# meld_fb.net
KiCad netlist of a schematic drawn in EAGLE
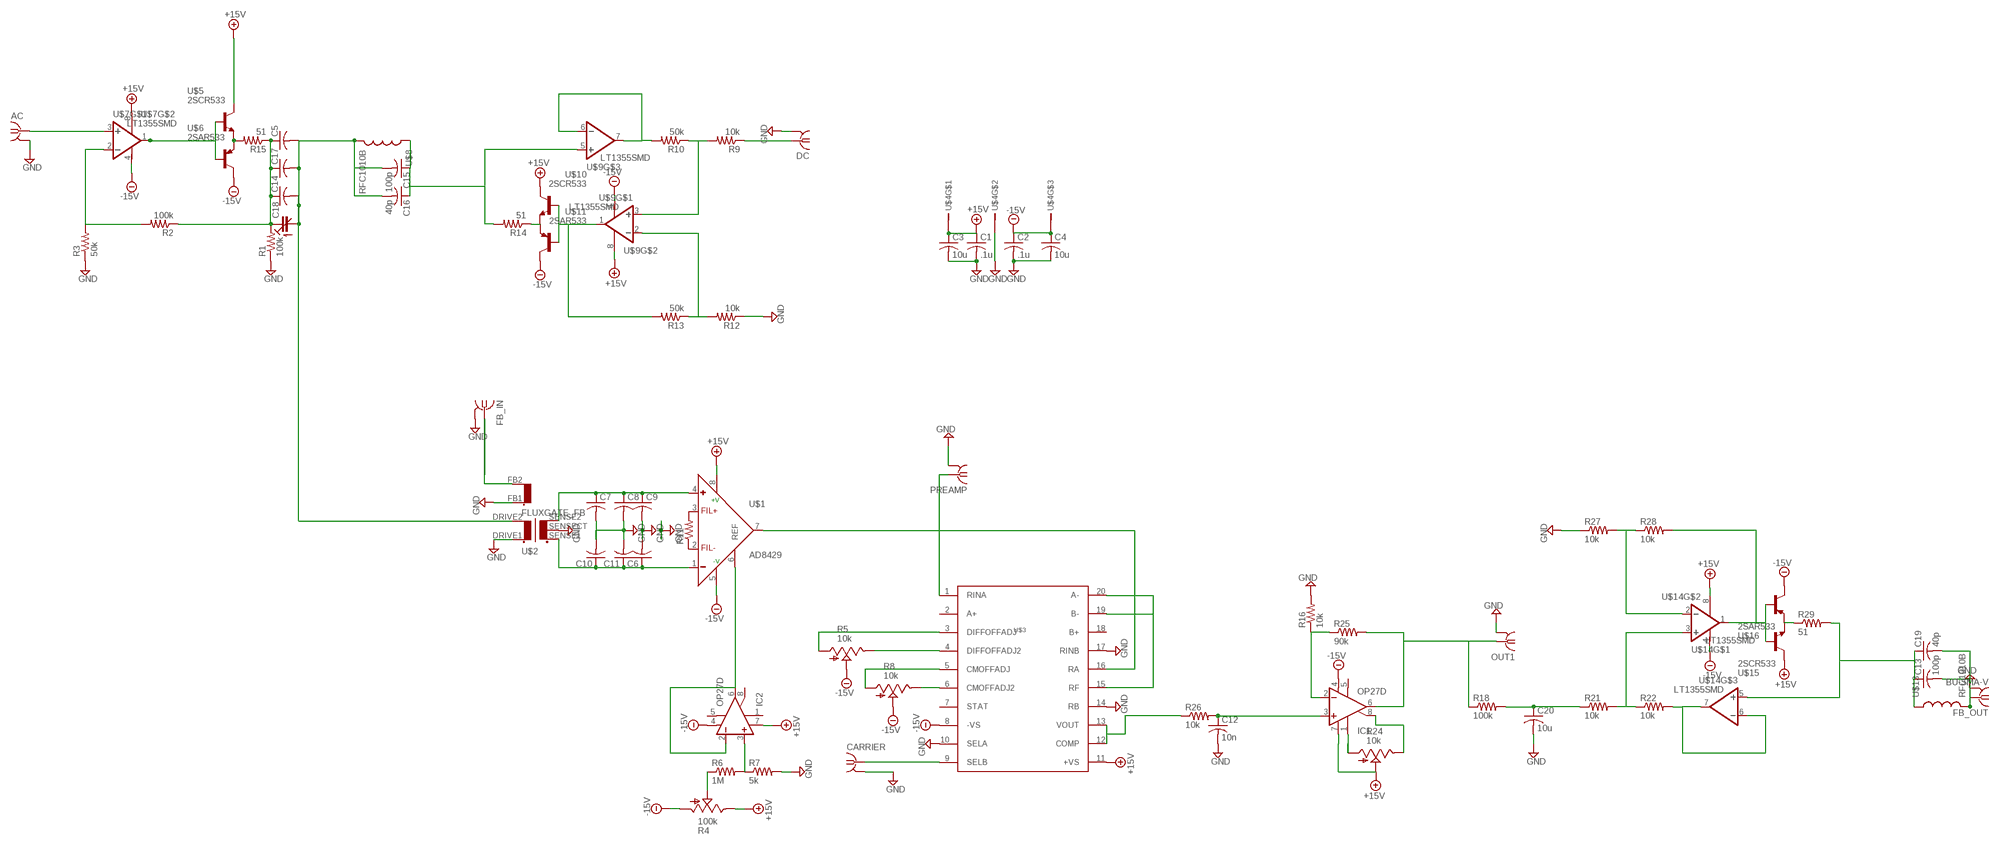
[diagram p0: schematic, sheet 1]

(export (version "E")
  (design (tool "Eeschema 10.0.6"))
  (components
    (comp (ref "AC")
      (value "SMA-142-0701-851/861")
      (footprint "eagle-import:J502-ND-142-0701-851_861")
      (fields (field (name "MF") "JOHNSON COMPONENTS") (field (name "MPN") "142-0701-851"))
      (libsource (lib "eagle-import") (part "SMA-142-0701-851/861"))
    )
    (comp (ref "C1")
      (value ".1u")
      (footprint "eagle-import:C1206")
      (libsource (lib "eagle-import") (part "C-USC1206"))
    )
    (comp (ref "C2")
      (value ".1u")
      (footprint "eagle-import:C1206")
      (libsource (lib "eagle-import") (part "C-USC1206"))
    )
    (comp (ref "C3")
      (value "10u")
      (footprint "eagle-import:C1206")
      (libsource (lib "eagle-import") (part "C-USC1206"))
    )
    (comp (ref "C4")
      (value "10u")
      (footprint "eagle-import:C1206")
      (libsource (lib "eagle-import") (part "C-USC1206"))
    )
    (comp (ref "C5")
      (value "C-USC0805")
      (footprint "eagle-import:C0805")
      (libsource (lib "eagle-import") (part "C-USC0805"))
    )
    (comp (ref "C6")
      (value "C-USC0805")
      (footprint "eagle-import:C0805")
      (libsource (lib "eagle-import") (part "C-USC0805"))
    )
    (comp (ref "C7")
      (value "C-USC0805")
      (footprint "eagle-import:C0805")
      (libsource (lib "eagle-import") (part "C-USC0805"))
    )
    (comp (ref "C8")
      (value "C-USC0805")
      (footprint "eagle-import:C0805")
      (libsource (lib "eagle-import") (part "C-USC0805"))
    )
    (comp (ref "C9")
      (value "C-USC0805")
      (footprint "eagle-import:C0805")
      (libsource (lib "eagle-import") (part "C-USC0805"))
    )
    (comp (ref "C10")
      (value "C-USC0805")
      (footprint "eagle-import:C0805")
      (libsource (lib "eagle-import") (part "C-USC0805"))
    )
    (comp (ref "C11")
      (value "C-USC0805")
      (footprint "eagle-import:C0805")
      (libsource (lib "eagle-import") (part "C-USC0805"))
    )
    (comp (ref "C12")
      (value "10n")
      (footprint "eagle-import:C0805")
      (libsource (lib "eagle-import") (part "C-USC0805"))
    )
    (comp (ref "C13")
      (value "100p")
      (footprint "eagle-import:C0805")
      (libsource (lib "eagle-import") (part "C-USC0805"))
    )
    (comp (ref "C14")
      (value "C-USC0805")
      (footprint "eagle-import:C0805")
      (libsource (lib "eagle-import") (part "C-USC0805"))
    )
    (comp (ref "C15")
      (value "100p")
      (footprint "eagle-import:C0805")
      (libsource (lib "eagle-import") (part "C-USC0805"))
    )
    (comp (ref "C16")
      (value "40p")
      (footprint "eagle-import:C0805")
      (libsource (lib "eagle-import") (part "C-USC0805"))
    )
    (comp (ref "C17")
      (value "C-USC0805")
      (footprint "eagle-import:C0805")
      (libsource (lib "eagle-import") (part "C-USC0805"))
    )
    (comp (ref "C18")
      (value "C-TRIMM")
      (footprint "eagle-import:SGC3S")
      (libsource (lib "eagle-import") (part "C-TRIMM"))
    )
    (comp (ref "C19")
      (value "40p")
      (footprint "eagle-import:C0805")
      (libsource (lib "eagle-import") (part "C-USC0805"))
    )
    (comp (ref "C20")
      (value "10u")
      (footprint "eagle-import:C1206")
      (libsource (lib "eagle-import") (part "C-USC1206"))
    )
    (comp (ref "CARRIER")
      (value "SMA-142-0701-851/861")
      (footprint "eagle-import:J502-ND-142-0701-851_861")
      (fields (field (name "MF") "JOHNSON COMPONENTS") (field (name "MPN") "142-0701-851"))
      (libsource (lib "eagle-import") (part "SMA-142-0701-851/861"))
    )
    (comp (ref "DC")
      (value "SMA-142-0701-851/861")
      (footprint "eagle-import:J502-ND-142-0701-851_861")
      (fields (field (name "MF") "JOHNSON COMPONENTS") (field (name "MPN") "142-0701-851"))
      (libsource (lib "eagle-import") (part "SMA-142-0701-851/861"))
    )
    (comp (ref "FB_IN")
      (value "SMA-142-0701-851/861")
      (footprint "eagle-import:J502-ND-142-0701-851_861")
      (fields (field (name "MF") "JOHNSON COMPONENTS") (field (name "MPN") "142-0701-851"))
      (libsource (lib "eagle-import") (part "SMA-142-0701-851/861"))
    )
    (comp (ref "FB_OUT")
      (value "BU-SMA-V")
      (footprint "eagle-import:BU-SMA-V")
      (libsource (lib "eagle-import") (part "BU-SMA-V"))
    )
    (comp (ref "IC1")
      (value "OP27D")
      (footprint "eagle-import:SO08")
      (libsource (lib "eagle-import") (part "OP27D"))
    )
    (comp (ref "IC2")
      (value "OP27D")
      (footprint "eagle-import:SO08")
      (libsource (lib "eagle-import") (part "OP27D"))
    )
    (comp (ref "OUT1")
      (value "SMA-142-0701-851/861")
      (footprint "eagle-import:J502-ND-142-0701-851_861")
      (fields (field (name "MF") "JOHNSON COMPONENTS") (field (name "MPN") "142-0701-851"))
      (libsource (lib "eagle-import") (part "SMA-142-0701-851/861"))
    )
    (comp (ref "PREAMP")
      (value "SMA-142-0701-851/861")
      (footprint "eagle-import:J502-ND-142-0701-851_861")
      (fields (field (name "MF") "JOHNSON COMPONENTS") (field (name "MPN") "142-0701-851"))
      (libsource (lib "eagle-import") (part "SMA-142-0701-851/861"))
    )
    (comp (ref "R1")
      (value "100k")
      (footprint "eagle-import:R0805")
      (libsource (lib "eagle-import") (part "R-US_R0805"))
    )
    (comp (ref "R2")
      (value "100k")
      (footprint "eagle-import:R0805")
      (libsource (lib "eagle-import") (part "R-US_R0805"))
    )
    (comp (ref "R3")
      (value "50k")
      (footprint "eagle-import:R0805")
      (libsource (lib "eagle-import") (part "R-US_R0805"))
    )
    (comp (ref "R4")
      (value "100k")
      (footprint "eagle-import:B64Y")
      (libsource (lib "eagle-import") (part "TRIM_US-B64Y"))
    )
    (comp (ref "R5")
      (value "10k")
      (footprint "eagle-import:B64Y")
      (libsource (lib "eagle-import") (part "TRIM_US-B64Y"))
    )
    (comp (ref "R6")
      (value "1M")
      (footprint "eagle-import:R0805")
      (libsource (lib "eagle-import") (part "R-US_R0805"))
    )
    (comp (ref "R7")
      (value "5k")
      (footprint "eagle-import:R0805")
      (libsource (lib "eagle-import") (part "R-US_R0805"))
    )
    (comp (ref "R8")
      (value "10k")
      (footprint "eagle-import:B64Y")
      (libsource (lib "eagle-import") (part "TRIM_US-B64Y"))
    )
    (comp (ref "R9")
      (value "10k")
      (footprint "eagle-import:R0805")
      (libsource (lib "eagle-import") (part "R-US_R0805"))
    )
    (comp (ref "R10")
      (value "50k")
      (footprint "eagle-import:R0805")
      (libsource (lib "eagle-import") (part "R-US_R0805"))
    )
    (comp (ref "R11")
      (value "R-US_R0805")
      (footprint "eagle-import:R0805")
      (libsource (lib "eagle-import") (part "R-US_R0805"))
    )
    (comp (ref "R12")
      (value "10k")
      (footprint "eagle-import:R0805")
      (libsource (lib "eagle-import") (part "R-US_R0805"))
    )
    (comp (ref "R13")
      (value "50k")
      (footprint "eagle-import:R0805")
      (libsource (lib "eagle-import") (part "R-US_R0805"))
    )
    (comp (ref "R14")
      (value "51")
      (footprint "eagle-import:R2512")
      (libsource (lib "eagle-import") (part "R-US_R2512"))
    )
    (comp (ref "R15")
      (value "51")
      (footprint "eagle-import:R2512")
      (libsource (lib "eagle-import") (part "R-US_R2512"))
    )
    (comp (ref "R16")
      (value "10k")
      (footprint "eagle-import:R0805")
      (libsource (lib "eagle-import") (part "resistor_R-US_R0805"))
    )
    (comp (ref "R18")
      (value "100k")
      (footprint "eagle-import:R0805")
      (libsource (lib "eagle-import") (part "resistor_R-US_R0805"))
    )
    (comp (ref "R21")
      (value "10k")
      (footprint "eagle-import:R0805")
      (libsource (lib "eagle-import") (part "R-US_R0805"))
    )
    (comp (ref "R22")
      (value "10k")
      (footprint "eagle-import:R0805")
      (libsource (lib "eagle-import") (part "R-US_R0805"))
    )
    (comp (ref "R24")
      (value "10k")
      (footprint "eagle-import:B64Y")
      (libsource (lib "eagle-import") (part "TRIM_US-B64Y"))
    )
    (comp (ref "R25")
      (value "90k")
      (footprint "eagle-import:R0805")
      (libsource (lib "eagle-import") (part "resistor_R-US_R0805"))
    )
    (comp (ref "R26")
      (value "10k")
      (footprint "eagle-import:R0805")
      (libsource (lib "eagle-import") (part "resistor_R-US_R0805"))
    )
    (comp (ref "R27")
      (value "10k")
      (footprint "eagle-import:R0805")
      (libsource (lib "eagle-import") (part "R-US_R0805"))
    )
    (comp (ref "R28")
      (value "10k")
      (footprint "eagle-import:R0805")
      (libsource (lib "eagle-import") (part "R-US_R0805"))
    )
    (comp (ref "R29")
      (value "51")
      (footprint "eagle-import:R2512")
      (libsource (lib "eagle-import") (part "R-US_R2512"))
    )
    (comp (ref "U$1")
      (value "AD8429")
      (footprint "eagle-import:SO8")
      (libsource (lib "eagle-import") (part "AD8428"))
    )
    (comp (ref "U$2")
      (value "FLUXGATE_FB")
      (footprint "eagle-import:PARA_FB")
      (libsource (lib "eagle-import") (part "FLUXGATE_FB"))
    )
    (comp (ref "U$3")
      (value "AD630")
      (footprint "eagle-import:SOIC20R")
      (libsource (lib "eagle-import") (part "AD630"))
    )
    (comp (ref "U$4")
      (value "B3B-AM")
      (footprint "eagle-import:B3B-AM")
      (libsource (lib "eagle-import") (part "B3B-AM"))
    )
    (comp (ref "U$5")
      (value "2SCR533")
      (footprint "eagle-import:SOT89-BCE")
      (libsource (lib "eagle-import") (part "2SCR533"))
    )
    (comp (ref "U$6")
      (value "2SAR533")
      (footprint "eagle-import:SOT89-BCE")
      (libsource (lib "eagle-import") (part "2SAR533"))
    )
    (comp (ref "U$7")
      (value "LT1355SMD")
      (footprint "eagle-import:SOIC8")
      (libsource (lib "eagle-import") (part "LT1355SMD"))
    )
    (comp (ref "U$8")
      (value "RFC1010B")
      (footprint "eagle-import:186KE")
      (libsource (lib "eagle-import") (part "RFC1010B"))
    )
    (comp (ref "U$9")
      (value "LT1355SMD")
      (footprint "eagle-import:SOIC8")
      (libsource (lib "eagle-import") (part "LT1355SMD"))
    )
    (comp (ref "U$10")
      (value "2SCR533")
      (footprint "eagle-import:SOT89-BCE")
      (libsource (lib "eagle-import") (part "2SCR533"))
    )
    (comp (ref "U$11")
      (value "2SAR533")
      (footprint "eagle-import:SOT89-BCE")
      (libsource (lib "eagle-import") (part "2SAR533"))
    )
    (comp (ref "U$13")
      (value "RFC1010B")
      (footprint "eagle-import:186KE")
      (libsource (lib "eagle-import") (part "RFC1010B"))
    )
    (comp (ref "U$14")
      (value "LT1355SMD")
      (footprint "eagle-import:SOIC8")
      (libsource (lib "eagle-import") (part "LT1355SMD"))
    )
    (comp (ref "U$15")
      (value "2SCR533")
      (footprint "eagle-import:SOT89-BCE")
      (libsource (lib "eagle-import") (part "2SCR533"))
    )
    (comp (ref "U$16")
      (value "2SAR533")
      (footprint "eagle-import:SOT89-BCE")
      (libsource (lib "eagle-import") (part "2SAR533"))
    )
  )
  (nets
    (net (code "1") (name "+15V") (class "Default")
      (node (ref "C1") (pin "1") (pinfunction "1_1") (pintype "passive"))
      (node (ref "C3") (pin "1") (pinfunction "1_1") (pintype "passive"))
      (node (ref "IC1") (pin "7") (pinfunction "V+_7") (pintype "power_in"))
      (node (ref "IC2") (pin "7") (pinfunction "V+_7") (pintype "power_in"))
      (node (ref "R24") (pin "S") (pinfunction "S_S") (pintype "passive"))
      (node (ref "R4") (pin "E") (pinfunction "E_E") (pintype "passive"))
      (node (ref "U$1") (pin "8") (pinfunction "+V_8") (pintype "power_in"))
      (node (ref "U$10") (pin "C") (pinfunction "C_C") (pintype "passive"))
      (node (ref "U$14") (pin "8") (pinfunction "V+_8") (pintype "power_in"))
      (node (ref "U$15") (pin "C") (pinfunction "C_C") (pintype "passive"))
      (node (ref "U$3") (pin "11") (pinfunction "+VS_11") (pintype "bidirectional"))
      (node (ref "U$4") (pin "1") (pinfunction "1_1") (pintype "passive"))
      (node (ref "U$5") (pin "C") (pinfunction "C_C") (pintype "passive"))
      (node (ref "U$7") (pin "8") (pinfunction "V+_8") (pintype "power_in"))
      (node (ref "U$9") (pin "8") (pinfunction "V+_8") (pintype "power_in"))
    )
    (net (code "2") (name "-15V") (class "Default")
      (node (ref "C2") (pin "1") (pinfunction "1_1") (pintype "passive"))
      (node (ref "C4") (pin "1") (pinfunction "1_1") (pintype "passive"))
      (node (ref "IC1") (pin "4") (pinfunction "V-_4") (pintype "power_in"))
      (node (ref "IC2") (pin "4") (pinfunction "V-_4") (pintype "power_in"))
      (node (ref "R4") (pin "A") (pinfunction "A_A") (pintype "passive"))
      (node (ref "R5") (pin "S") (pinfunction "S_S") (pintype "passive"))
      (node (ref "R8") (pin "S") (pinfunction "S_S") (pintype "passive"))
      (node (ref "U$1") (pin "5") (pinfunction "-V_5") (pintype "power_in"))
      (node (ref "U$11") (pin "C") (pinfunction "C_C") (pintype "passive"))
      (node (ref "U$14") (pin "4") (pinfunction "V-_4") (pintype "power_in"))
      (node (ref "U$16") (pin "C") (pinfunction "C_C") (pintype "passive"))
      (node (ref "U$3") (pin "8") (pinfunction "-VS_8") (pintype "bidirectional"))
      (node (ref "U$4") (pin "3") (pinfunction "1_3") (pintype "passive"))
      (node (ref "U$6") (pin "C") (pinfunction "C_C") (pintype "passive"))
      (node (ref "U$7") (pin "4") (pinfunction "V-_4") (pintype "power_in"))
      (node (ref "U$9") (pin "4") (pinfunction "V-_4") (pintype "power_in"))
    )
    (net (code "3") (name "GND") (class "Default")
      (node (ref "AC") (pin "G@1") (pinfunction "2_G@1") (pintype "passive"))
      (node (ref "AC") (pin "G@2") (pinfunction "2_G@2") (pintype "passive"))
      (node (ref "AC") (pin "G@3") (pinfunction "2_G@3") (pintype "passive"))
      (node (ref "AC") (pin "G@4") (pinfunction "2_G@4") (pintype "passive"))
      (node (ref "C1") (pin "2") (pinfunction "2_2") (pintype "passive"))
      (node (ref "C10") (pin "2") (pinfunction "2_2") (pintype "passive"))
      (node (ref "C11") (pin "2") (pinfunction "2_2") (pintype "passive"))
      (node (ref "C12") (pin "2") (pinfunction "2_2") (pintype "passive"))
      (node (ref "C2") (pin "2") (pinfunction "2_2") (pintype "passive"))
      (node (ref "C20") (pin "2") (pinfunction "2_2") (pintype "passive"))
      (node (ref "C3") (pin "2") (pinfunction "2_2") (pintype "passive"))
      (node (ref "C4") (pin "2") (pinfunction "2_2") (pintype "passive"))
      (node (ref "C6") (pin "2") (pinfunction "2_2") (pintype "passive"))
      (node (ref "C7") (pin "2") (pinfunction "2_2") (pintype "passive"))
      (node (ref "C8") (pin "2") (pinfunction "2_2") (pintype "passive"))
      (node (ref "C9") (pin "2") (pinfunction "2_2") (pintype "passive"))
      (node (ref "CARRIER") (pin "G@1") (pinfunction "2_G@1") (pintype "passive"))
      (node (ref "CARRIER") (pin "G@2") (pinfunction "2_G@2") (pintype "passive"))
      (node (ref "CARRIER") (pin "G@3") (pinfunction "2_G@3") (pintype "passive"))
      (node (ref "CARRIER") (pin "G@4") (pinfunction "2_G@4") (pintype "passive"))
      (node (ref "DC") (pin "G@1") (pinfunction "2_G@1") (pintype "passive"))
      (node (ref "DC") (pin "G@2") (pinfunction "2_G@2") (pintype "passive"))
      (node (ref "DC") (pin "G@3") (pinfunction "2_G@3") (pintype "passive"))
      (node (ref "DC") (pin "G@4") (pinfunction "2_G@4") (pintype "passive"))
      (node (ref "FB_IN") (pin "G@1") (pinfunction "2_G@1") (pintype "passive"))
      (node (ref "FB_IN") (pin "G@2") (pinfunction "2_G@2") (pintype "passive"))
      (node (ref "FB_IN") (pin "G@3") (pinfunction "2_G@3") (pintype "passive"))
      (node (ref "FB_IN") (pin "G@4") (pinfunction "2_G@4") (pintype "passive"))
      (node (ref "FB_OUT") (pin "2") (pinfunction "2_2") (pintype "passive"))
      (node (ref "FB_OUT") (pin "3") (pinfunction "2_3") (pintype "passive"))
      (node (ref "FB_OUT") (pin "4") (pinfunction "2_4") (pintype "passive"))
      (node (ref "FB_OUT") (pin "5") (pinfunction "2_5") (pintype "passive"))
      (node (ref "OUT1") (pin "G@1") (pinfunction "2_G@1") (pintype "passive"))
      (node (ref "OUT1") (pin "G@2") (pinfunction "2_G@2") (pintype "passive"))
      (node (ref "OUT1") (pin "G@3") (pinfunction "2_G@3") (pintype "passive"))
      (node (ref "OUT1") (pin "G@4") (pinfunction "2_G@4") (pintype "passive"))
      (node (ref "PREAMP") (pin "G@1") (pinfunction "2_G@1") (pintype "passive"))
      (node (ref "PREAMP") (pin "G@2") (pinfunction "2_G@2") (pintype "passive"))
      (node (ref "PREAMP") (pin "G@3") (pinfunction "2_G@3") (pintype "passive"))
      (node (ref "PREAMP") (pin "G@4") (pinfunction "2_G@4") (pintype "passive"))
      (node (ref "R1") (pin "1") (pinfunction "1_1") (pintype "passive"))
      (node (ref "R12") (pin "1") (pinfunction "1_1") (pintype "passive"))
      (node (ref "R16") (pin "2") (pinfunction "2_2") (pintype "passive"))
      (node (ref "R27") (pin "1") (pinfunction "1_1") (pintype "passive"))
      (node (ref "R3") (pin "1") (pinfunction "1_1") (pintype "passive"))
      (node (ref "R7") (pin "2") (pinfunction "2_2") (pintype "passive"))
      (node (ref "U$2") (pin "DRIVE1") (pinfunction "1_DRIVE1") (pintype "passive"))
      (node (ref "U$2") (pin "FB1") (pinfunction "6_FB1") (pintype "passive"))
      (node (ref "U$2") (pin "SENSECT") (pinfunction "4_SENSECT") (pintype "passive"))
      (node (ref "U$3") (pin "10") (pinfunction "SELA_10") (pintype "bidirectional"))
      (node (ref "U$3") (pin "14") (pinfunction "RB_14") (pintype "bidirectional"))
      (node (ref "U$3") (pin "17") (pinfunction "RINB_17") (pintype "bidirectional"))
      (node (ref "U$4") (pin "2") (pinfunction "1_2") (pintype "passive"))
    )
    (net (code "4") (name "Net-(C18-A)") (class "Default")
      (node (ref "C14") (pin "2") (pinfunction "2_2") (pintype "passive"))
      (node (ref "C15") (pin "2") (pinfunction "2_2") (pintype "passive"))
      (node (ref "C16") (pin "2") (pinfunction "2_2") (pintype "passive"))
      (node (ref "C17") (pin "2") (pinfunction "2_2") (pintype "passive"))
      (node (ref "C18") (pin "P$1") (pinfunction "A_P$1") (pintype "passive"))
      (node (ref "C5") (pin "2") (pinfunction "2_2") (pintype "passive"))
      (node (ref "U$2") (pin "DRIVE2") (pinfunction "2_DRIVE2") (pintype "passive"))
      (node (ref "U$8") (pin "P$2") (pinfunction "2_P$2") (pintype "passive"))
    )
    (net (code "5") (name "Net-(C18-E)") (class "Default")
      (node (ref "C14") (pin "1") (pinfunction "1_1") (pintype "passive"))
      (node (ref "C17") (pin "1") (pinfunction "1_1") (pintype "passive"))
      (node (ref "C18") (pin "P$2") (pinfunction "E_P$2") (pintype "passive"))
      (node (ref "C5") (pin "1") (pinfunction "1_1") (pintype "passive"))
      (node (ref "R1") (pin "2") (pinfunction "2_2") (pintype "passive"))
      (node (ref "R15") (pin "1") (pinfunction "1_1") (pintype "passive"))
      (node (ref "R2") (pin "1") (pinfunction "1_1") (pintype "passive"))
    )
    (net (code "6") (name "Net-(C20-Pad1)") (class "Default")
      (node (ref "C20") (pin "1") (pinfunction "1_1") (pintype "passive"))
      (node (ref "R18") (pin "2") (pinfunction "2_2") (pintype "passive"))
      (node (ref "R21") (pin "1") (pinfunction "1_1") (pintype "passive"))
    )
    (net (code "7") (name "Net-(DC-Pad1)") (class "Default")
      (node (ref "DC") (pin "1") (pinfunction "1_1") (pintype "passive"))
      (node (ref "R9") (pin "1") (pinfunction "1_1") (pintype "passive"))
    )
    (net (code "8") (name "Net-(IC1-+IN)") (class "Default")
      (node (ref "C12") (pin "1") (pinfunction "1_1") (pintype "passive"))
      (node (ref "IC1") (pin "3") (pinfunction "+IN_3") (pintype "input"))
      (node (ref "R26") (pin "2") (pinfunction "2_2") (pintype "passive"))
    )
    (net (code "9") (name "Net-(IC1--IN)") (class "Default")
      (node (ref "IC1") (pin "2") (pinfunction "-IN_2") (pintype "input"))
      (node (ref "R16") (pin "1") (pinfunction "1_1") (pintype "passive"))
      (node (ref "R25") (pin "1") (pinfunction "1_1") (pintype "passive"))
    )
    (net (code "10") (name "Net-(IC1-ON1)") (class "Default")
      (node (ref "IC1") (pin "1") (pinfunction "ON1_1") (pintype "passive"))
      (node (ref "R24") (pin "A") (pinfunction "A_A") (pintype "passive"))
    )
    (net (code "11") (name "Net-(IC1-ON2)") (class "Default")
      (node (ref "IC1") (pin "8") (pinfunction "ON2_8") (pintype "passive"))
      (node (ref "R24") (pin "E") (pinfunction "E_E") (pintype "passive"))
    )
    (net (code "12") (name "Net-(IC1-OUT)") (class "Default")
      (node (ref "IC1") (pin "6") (pinfunction "OUT_6") (pintype "output"))
      (node (ref "OUT1") (pin "1") (pinfunction "1_1") (pintype "passive"))
      (node (ref "R18") (pin "1") (pinfunction "1_1") (pintype "passive"))
      (node (ref "R25") (pin "2") (pinfunction "2_2") (pintype "passive"))
    )
    (net (code "13") (name "Net-(IC2-+IN)") (class "Default")
      (node (ref "IC2") (pin "3") (pinfunction "+IN_3") (pintype "input"))
      (node (ref "R6") (pin "2") (pinfunction "2_2") (pintype "passive"))
      (node (ref "R7") (pin "1") (pinfunction "1_1") (pintype "passive"))
    )
    (net (code "14") (name "Net-(IC2--IN)") (class "Default")
      (node (ref "IC2") (pin "2") (pinfunction "-IN_2") (pintype "input"))
      (node (ref "IC2") (pin "6") (pinfunction "OUT_6") (pintype "output"))
      (node (ref "U$1") (pin "6") (pinfunction "REF_6") (pintype "passive"))
    )
    (net (code "15") (name "Net-(R4-PadS)") (class "Default")
      (node (ref "R4") (pin "S") (pinfunction "S_S") (pintype "passive"))
      (node (ref "R6") (pin "1") (pinfunction "1_1") (pintype "passive"))
    )
    (net (code "16") (name "Net-(R14-Pad1)") (class "Default")
      (node (ref "R14") (pin "1") (pinfunction "1_1") (pintype "passive"))
      (node (ref "U$10") (pin "E") (pinfunction "E_E") (pintype "passive"))
      (node (ref "U$11") (pin "E") (pinfunction "E_E") (pintype "passive"))
    )
    (net (code "17") (name "Net-(R15-Pad2)") (class "Default")
      (node (ref "R15") (pin "2") (pinfunction "2_2") (pintype "passive"))
      (node (ref "U$5") (pin "E") (pinfunction "E_E") (pintype "passive"))
      (node (ref "U$6") (pin "E") (pinfunction "E_E") (pintype "passive"))
    )
    (net (code "18") (name "Net-(R29-Pad1)") (class "Default")
      (node (ref "R29") (pin "1") (pinfunction "1_1") (pintype "passive"))
      (node (ref "U$15") (pin "E") (pinfunction "E_E") (pintype "passive"))
      (node (ref "U$16") (pin "E") (pinfunction "E_E") (pintype "passive"))
    )
    (net (code "19") (name "Net-(U$1-+)") (class "Default")
      (node (ref "C7") (pin "1") (pinfunction "1_1") (pintype "passive"))
      (node (ref "C8") (pin "1") (pinfunction "1_1") (pintype "passive"))
      (node (ref "C9") (pin "1") (pinfunction "1_1") (pintype "passive"))
      (node (ref "U$1") (pin "4") (pinfunction "+_4") (pintype "input"))
      (node (ref "U$2") (pin "SENSE2") (pinfunction "3_SENSE2") (pintype "passive"))
    )
    (net (code "20") (name "Net-(U$1--)") (class "Default")
      (node (ref "C10") (pin "1") (pinfunction "1_1") (pintype "passive"))
      (node (ref "C11") (pin "1") (pinfunction "1_1") (pintype "passive"))
      (node (ref "C6") (pin "1") (pinfunction "1_1") (pintype "passive"))
      (node (ref "U$1") (pin "1") (pinfunction "-_1") (pintype "input"))
      (node (ref "U$2") (pin "SENSE1") (pinfunction "5_SENSE1") (pintype "passive"))
    )
    (net (code "21") (name "Net-(U$1-FIL+)") (class "Default")
      (node (ref "R11") (pin "2") (pinfunction "2_2") (pintype "passive"))
      (node (ref "U$1") (pin "3") (pinfunction "FIL+_3") (pintype "passive"))
    )
    (net (code "22") (name "Net-(U$1-FIL-)") (class "Default")
      (node (ref "R11") (pin "1") (pinfunction "1_1") (pintype "passive"))
      (node (ref "U$1") (pin "2") (pinfunction "FIL-_2") (pintype "passive"))
    )
    (net (code "23") (name "Net-(U$1-OUT)") (class "Default")
      (node (ref "PREAMP") (pin "1") (pinfunction "1_1") (pintype "passive"))
      (node (ref "U$1") (pin "7") (pinfunction "OUT_7") (pintype "output"))
      (node (ref "U$3") (pin "1") (pinfunction "RINA_1") (pintype "bidirectional"))
      (node (ref "U$3") (pin "16") (pinfunction "RA_16") (pintype "bidirectional"))
    )
    (net (code "24") (name "Net-(U$2-7)") (class "Default")
      (node (ref "FB_IN") (pin "1") (pinfunction "1_1") (pintype "passive"))
      (node (ref "U$2") (pin "FB2") (pinfunction "7_FB2") (pintype "passive"))
    )
    (net (code "25") (name "Net-(U$3-A-)") (class "Default")
      (node (ref "U$3") (pin "15") (pinfunction "RF_15") (pintype "bidirectional"))
      (node (ref "U$3") (pin "19") (pinfunction "B-_19") (pintype "bidirectional"))
      (node (ref "U$3") (pin "20") (pinfunction "A-_20") (pintype "bidirectional"))
    )
    (net (code "26") (name "Net-(U$3-CMOFFADJ)") (class "Default")
      (node (ref "R8") (pin "A") (pinfunction "A_A") (pintype "passive"))
      (node (ref "U$3") (pin "5") (pinfunction "CMOFFADJ_5") (pintype "bidirectional"))
    )
    (net (code "27") (name "Net-(U$3-CMOFFADJ2)") (class "Default")
      (node (ref "R8") (pin "E") (pinfunction "E_E") (pintype "passive"))
      (node (ref "U$3") (pin "6") (pinfunction "CMOFFADJ2_6") (pintype "bidirectional"))
    )
    (net (code "28") (name "Net-(U$3-COMP)") (class "Default")
      (node (ref "R26") (pin "1") (pinfunction "1_1") (pintype "passive"))
      (node (ref "U$3") (pin "12") (pinfunction "COMP_12") (pintype "bidirectional"))
      (node (ref "U$3") (pin "13") (pinfunction "VOUT_13") (pintype "bidirectional"))
    )
    (net (code "29") (name "Net-(U$3-DIFFOFFADJ)") (class "Default")
      (node (ref "R5") (pin "A") (pinfunction "A_A") (pintype "passive"))
      (node (ref "U$3") (pin "3") (pinfunction "DIFFOFFADJ_3") (pintype "bidirectional"))
    )
    (net (code "30") (name "Net-(U$3-DIFFOFFADJ2)") (class "Default")
      (node (ref "R5") (pin "E") (pinfunction "E_E") (pintype "passive"))
      (node (ref "U$3") (pin "4") (pinfunction "DIFFOFFADJ2_4") (pintype "bidirectional"))
    )
    (net (code "31") (name "Net-(U$3-SELB)") (class "Default")
      (node (ref "CARRIER") (pin "1") (pinfunction "1_1") (pintype "passive"))
      (node (ref "U$3") (pin "9") (pinfunction "SELB_9") (pintype "bidirectional"))
    )
    (net (code "32") (name "Net-(U$7A-+IN)") (class "Default")
      (node (ref "AC") (pin "1") (pinfunction "1_1") (pintype "passive"))
      (node (ref "U$7") (pin "3") (pinfunction "+IN_3") (pintype "input"))
    )
    (net (code "33") (name "Net-(U$7A--IN)") (class "Default")
      (node (ref "R2") (pin "2") (pinfunction "2_2") (pintype "passive"))
      (node (ref "R3") (pin "2") (pinfunction "2_2") (pintype "passive"))
      (node (ref "U$7") (pin "2") (pinfunction "-IN_2") (pintype "input"))
    )
    (net (code "34") (name "Net-(U$7A-OUT)") (class "Default")
      (node (ref "U$5") (pin "B") (pinfunction "B_B") (pintype "passive"))
      (node (ref "U$6") (pin "B") (pinfunction "B_B") (pintype "passive"))
      (node (ref "U$7") (pin "1") (pinfunction "OUT_1") (pintype "output"))
    )
    (net (code "35") (name "Net-(U$8-1)") (class "Default")
      (node (ref "C15") (pin "1") (pinfunction "1_1") (pintype "passive"))
      (node (ref "C16") (pin "1") (pinfunction "1_1") (pintype "passive"))
      (node (ref "R14") (pin "2") (pinfunction "2_2") (pintype "passive"))
      (node (ref "U$8") (pin "P$1") (pinfunction "1_P$1") (pintype "passive"))
      (node (ref "U$9") (pin "5") (pinfunction "+IN_5") (pintype "input"))
    )
    (net (code "36") (name "Net-(U$9A-+IN)") (class "Default")
      (node (ref "R10") (pin "1") (pinfunction "1_1") (pintype "passive"))
      (node (ref "R9") (pin "2") (pinfunction "2_2") (pintype "passive"))
      (node (ref "U$9") (pin "3") (pinfunction "+IN_3") (pintype "input"))
    )
    (net (code "37") (name "Net-(U$9A--IN)") (class "Default")
      (node (ref "R12") (pin "2") (pinfunction "2_2") (pintype "passive"))
      (node (ref "R13") (pin "1") (pinfunction "1_1") (pintype "passive"))
      (node (ref "U$9") (pin "2") (pinfunction "-IN_2") (pintype "input"))
    )
    (net (code "38") (name "Net-(U$9A-OUT)") (class "Default")
      (node (ref "R13") (pin "2") (pinfunction "2_2") (pintype "passive"))
      (node (ref "U$10") (pin "B") (pinfunction "B_B") (pintype "passive"))
      (node (ref "U$11") (pin "B") (pinfunction "B_B") (pintype "passive"))
      (node (ref "U$9") (pin "1") (pinfunction "OUT_1") (pintype "output"))
    )
    (net (code "39") (name "Net-(U$9C--IN)") (class "Default")
      (node (ref "R10") (pin "2") (pinfunction "2_2") (pintype "passive"))
      (node (ref "U$9") (pin "6") (pinfunction "-IN_6") (pintype "input"))
      (node (ref "U$9") (pin "7") (pinfunction "OUT_7") (pintype "output"))
    )
    (net (code "40") (name "Net-(U$13-1)") (class "Default")
      (node (ref "C13") (pin "1") (pinfunction "1_1") (pintype "passive"))
      (node (ref "C19") (pin "1") (pinfunction "1_1") (pintype "passive"))
      (node (ref "R29") (pin "2") (pinfunction "2_2") (pintype "passive"))
      (node (ref "U$13") (pin "P$1") (pinfunction "1_P$1") (pintype "passive"))
      (node (ref "U$14") (pin "5") (pinfunction "+IN_5") (pintype "input"))
    )
    (net (code "41") (name "Net-(U$13-2)") (class "Default")
      (node (ref "C13") (pin "2") (pinfunction "2_2") (pintype "passive"))
      (node (ref "C19") (pin "2") (pinfunction "2_2") (pintype "passive"))
      (node (ref "FB_OUT") (pin "1") (pinfunction "1_1") (pintype "passive"))
      (node (ref "U$13") (pin "P$2") (pinfunction "2_P$2") (pintype "passive"))
    )
    (net (code "42") (name "Net-(U$14A-+IN)") (class "Default")
      (node (ref "R21") (pin "2") (pinfunction "2_2") (pintype "passive"))
      (node (ref "R22") (pin "1") (pinfunction "1_1") (pintype "passive"))
      (node (ref "U$14") (pin "3") (pinfunction "+IN_3") (pintype "input"))
    )
    (net (code "43") (name "Net-(U$14A--IN)") (class "Default")
      (node (ref "R27") (pin "2") (pinfunction "2_2") (pintype "passive"))
      (node (ref "R28") (pin "1") (pinfunction "1_1") (pintype "passive"))
      (node (ref "U$14") (pin "2") (pinfunction "-IN_2") (pintype "input"))
    )
    (net (code "44") (name "Net-(U$14A-OUT)") (class "Default")
      (node (ref "R28") (pin "2") (pinfunction "2_2") (pintype "passive"))
      (node (ref "U$14") (pin "1") (pinfunction "OUT_1") (pintype "output"))
      (node (ref "U$15") (pin "B") (pinfunction "B_B") (pintype "passive"))
      (node (ref "U$16") (pin "B") (pinfunction "B_B") (pintype "passive"))
    )
    (net (code "45") (name "Net-(U$14C--IN)") (class "Default")
      (node (ref "R22") (pin "2") (pinfunction "2_2") (pintype "passive"))
      (node (ref "U$14") (pin "6") (pinfunction "-IN_6") (pintype "input"))
      (node (ref "U$14") (pin "7") (pinfunction "OUT_7") (pintype "output"))
    )
    (net (code "46") (name "unconnected-(IC1-OPT-Pad5)") (class "Default")
      (node (ref "IC1") (pin "5") (pinfunction "OPT_5") (pintype "passive"))
    )
    (net (code "47") (name "unconnected-(IC2-ON1-Pad1)") (class "Default")
      (node (ref "IC2") (pin "1") (pinfunction "ON1_1") (pintype "passive"))
    )
    (net (code "48") (name "unconnected-(IC2-ON2-Pad8)") (class "Default")
      (node (ref "IC2") (pin "8") (pinfunction "ON2_8") (pintype "passive"))
    )
    (net (code "49") (name "unconnected-(IC2-OPT-Pad5)") (class "Default")
      (node (ref "IC2") (pin "5") (pinfunction "OPT_5") (pintype "passive"))
    )
    (net (code "50") (name "unconnected-(U$3-A+-Pad2)") (class "Default")
      (node (ref "U$3") (pin "2") (pinfunction "A+_2") (pintype "bidirectional"))
    )
    (net (code "51") (name "unconnected-(U$3-B+-Pad18)") (class "Default")
      (node (ref "U$3") (pin "18") (pinfunction "B+_18") (pintype "bidirectional"))
    )
    (net (code "52") (name "unconnected-(U$3-STAT-Pad7)") (class "Default")
      (node (ref "U$3") (pin "7") (pinfunction "STAT_7") (pintype "bidirectional"))
    )
  )
)
